# ProProject_Sheet1_2025-12-18.net
KiCad netlist of a schematic drawn in EasyEDA Pro
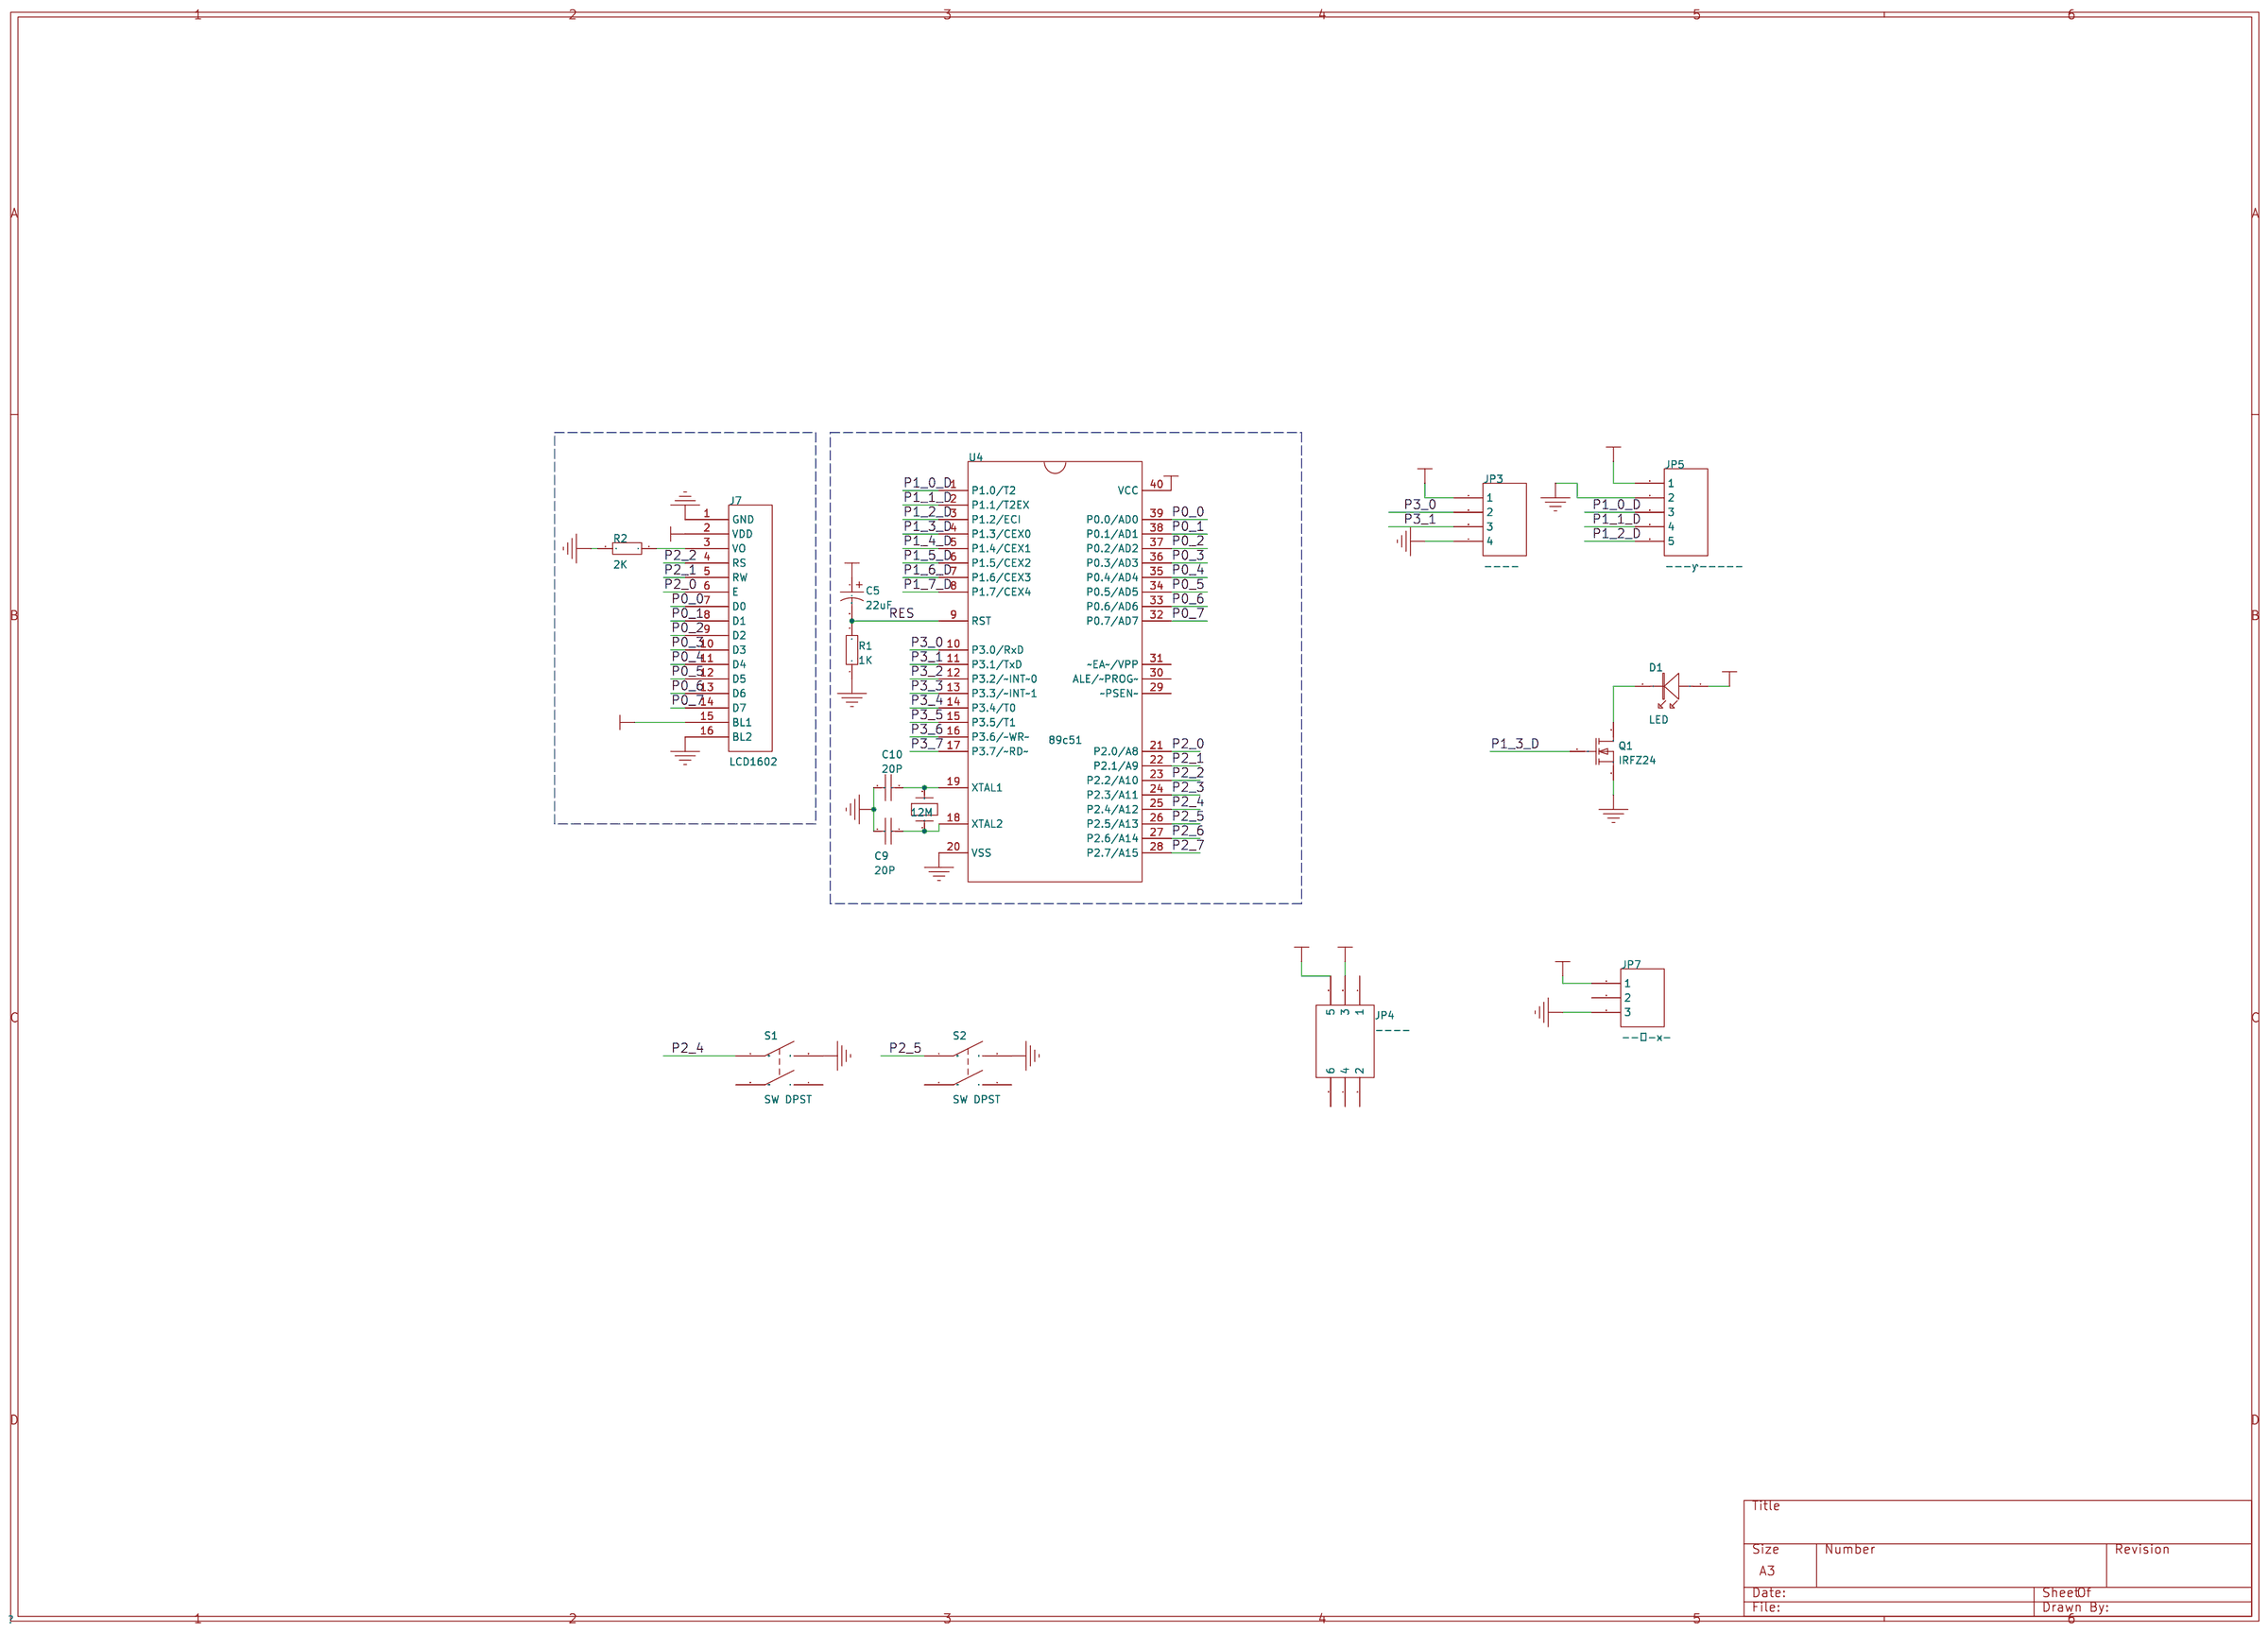
[diagram p0: schematic sheet]

(export (version "E")
  (design (tool "Eeschema 10.0.6"))
  (components
    (comp (ref "C5")
      (value "22uF")
      (description "Polarized Capacitor (Radial)")
      (fields (field (name "Publisher") "Altium Limited"))
      (libsource (lib "easyedapro") (part "Cap Pol1"))
    )
    (comp (ref "C9") (value "20P") (description "Capacitor") (libsource (lib "easyedapro") (part "CAP")))
    (comp (ref "C10") (value "20P") (description "Capacitor") (libsource (lib "easyedapro") (part "CAP")))
    (comp (ref "D1") (value "LED") (libsource (lib "easyedapro") (part "LED")))
    (comp (ref "J7") (value "LCD1602") (libsource (lib "easyedapro") (part "LCD1602")))
    (comp (ref "JP3")
      (value "----")
      (description "4 Pin Header")
      (libsource (lib "easyedapro") (part "4 HEADER"))
    )
    (comp (ref "JP4") (value "----") (libsource (lib "easyedapro") (part "HEADER 3X2")))
    (comp (ref "JP5") (value "---ƴ-----") (libsource (lib "easyedapro") (part "HEADER 5")))
    (comp (ref "JP7") (value "--Դ-ӿ-") (libsource (lib "easyedapro") (part "HEADER 3")))
    (comp (ref "Q1")
      (value "IRFZ24")
      (description "N-Channel MOSFET")
      (libsource (lib "easyedapro") (part "IRFZ24"))
    )
    (comp (ref "R1")
      (value "1K")
      (description "Resistor")
      (fields (field (name "Publisher") "Altium Limited"))
      (libsource (lib "easyedapro") (part "Res2"))
    )
    (comp (ref "R2")
      (value "2K")
      (description "Resistor")
      (fields (field (name "Publisher") "Altium Limited"))
      (libsource (lib "easyedapro") (part "Res2"))
    )
    (comp (ref "S1") (value "SW DPST") (libsource (lib "easyedapro") (part "SW DPST")))
    (comp (ref "S2") (value "SW DPST") (libsource (lib "easyedapro") (part "SW DPST")))
    (comp (ref "U4") (value "89c51") (libsource (lib "easyedapro") (part "89c51")))
    (comp (ref "Y4") (value "12M") (description "Crystal") (libsource (lib "easyedapro") (part "CRYSTAL")))
  )
  (nets
    (net (code "1") (name "/P0_0") (class "Default")
      (node (ref "J7") (pin "7") (pinfunction "D0_7") (pintype "unspecified"))
      (node (ref "U4") (pin "39") (pinfunction "P0.0/AD0_39") (pintype "bidirectional"))
    )
    (net (code "2") (name "/P0_1") (class "Default")
      (node (ref "J7") (pin "8") (pinfunction "D1_8") (pintype "unspecified"))
      (node (ref "U4") (pin "38") (pinfunction "P0.1/AD1_38") (pintype "bidirectional"))
    )
    (net (code "3") (name "/P0_2") (class "Default")
      (node (ref "J7") (pin "9") (pinfunction "D2_9") (pintype "unspecified"))
      (node (ref "U4") (pin "37") (pinfunction "P0.2/AD2_37") (pintype "bidirectional"))
    )
    (net (code "4") (name "/P0_3") (class "Default")
      (node (ref "J7") (pin "10") (pinfunction "D3_10") (pintype "unspecified"))
      (node (ref "U4") (pin "36") (pinfunction "P0.3/AD3_36") (pintype "bidirectional"))
    )
    (net (code "5") (name "/P0_4") (class "Default")
      (node (ref "J7") (pin "11") (pinfunction "D4_11") (pintype "unspecified"))
      (node (ref "U4") (pin "35") (pinfunction "P0.4/AD4_35") (pintype "bidirectional"))
    )
    (net (code "6") (name "/P0_5") (class "Default")
      (node (ref "J7") (pin "12") (pinfunction "D5_12") (pintype "unspecified"))
      (node (ref "U4") (pin "34") (pinfunction "P0.5/AD5_34") (pintype "bidirectional"))
    )
    (net (code "7") (name "/P0_6") (class "Default")
      (node (ref "J7") (pin "13") (pinfunction "D6_13") (pintype "unspecified"))
      (node (ref "U4") (pin "33") (pinfunction "P0.6/AD6_33") (pintype "bidirectional"))
    )
    (net (code "8") (name "/P0_7") (class "Default")
      (node (ref "J7") (pin "14") (pinfunction "D7_14") (pintype "unspecified"))
      (node (ref "U4") (pin "32") (pinfunction "P0.7/AD7_32") (pintype "bidirectional"))
    )
    (net (code "9") (name "/P1_0_D") (class "Default")
      (node (ref "JP5") (pin "3") (pinfunction "3_3") (pintype "unspecified"))
      (node (ref "U4") (pin "1") (pinfunction "P1.0/T2_1") (pintype "bidirectional"))
    )
    (net (code "10") (name "/P1_1_D") (class "Default")
      (node (ref "JP5") (pin "4") (pinfunction "4_4") (pintype "unspecified"))
      (node (ref "U4") (pin "2") (pinfunction "P1.1/T2EX_2") (pintype "bidirectional"))
    )
    (net (code "11") (name "/P1_2_D") (class "Default")
      (node (ref "JP5") (pin "5") (pinfunction "5_5") (pintype "unspecified"))
      (node (ref "U4") (pin "3") (pinfunction "P1.2/ECI_3") (pintype "bidirectional"))
    )
    (net (code "12") (name "/P1_3_D") (class "Default")
      (node (ref "Q1") (pin "1") (pinfunction "G_1") (pintype "input"))
      (node (ref "U4") (pin "4") (pinfunction "P1.3/CEX0_4") (pintype "bidirectional"))
    )
    (net (code "13") (name "/P1_4_D") (class "Default")
      (node (ref "U4") (pin "5") (pinfunction "P1.4/CEX1_5") (pintype "bidirectional"))
    )
    (net (code "14") (name "/P1_5_D") (class "Default")
      (node (ref "U4") (pin "6") (pinfunction "P1.5/CEX2_6") (pintype "bidirectional"))
    )
    (net (code "15") (name "/P1_6_D") (class "Default")
      (node (ref "U4") (pin "7") (pinfunction "P1.6/CEX3_7") (pintype "bidirectional"))
    )
    (net (code "16") (name "/P1_7_D") (class "Default")
      (node (ref "U4") (pin "8") (pinfunction "P1.7/CEX4_8") (pintype "bidirectional"))
    )
    (net (code "17") (name "/P2_0") (class "Default")
      (node (ref "J7") (pin "6") (pinfunction "E_6") (pintype "unspecified"))
      (node (ref "U4") (pin "21") (pinfunction "P2.0/A8_21") (pintype "bidirectional"))
    )
    (net (code "18") (name "/P2_1") (class "Default")
      (node (ref "J7") (pin "5") (pinfunction "RW_5") (pintype "unspecified"))
      (node (ref "U4") (pin "22") (pinfunction "P2.1/A9_22") (pintype "bidirectional"))
    )
    (net (code "19") (name "/P2_2") (class "Default")
      (node (ref "J7") (pin "4") (pinfunction "RS_4") (pintype "unspecified"))
      (node (ref "U4") (pin "23") (pinfunction "P2.2/A10_23") (pintype "bidirectional"))
    )
    (net (code "20") (name "/P2_3") (class "Default")
      (node (ref "U4") (pin "24") (pinfunction "P2.3/A11_24") (pintype "bidirectional"))
    )
    (net (code "21") (name "/P2_4") (class "Default")
      (node (ref "S1") (pin "1") (pinfunction "COMMON1_1") (pintype "unspecified"))
      (node (ref "U4") (pin "25") (pinfunction "P2.4/A12_25") (pintype "bidirectional"))
    )
    (net (code "22") (name "/P2_5") (class "Default")
      (node (ref "S2") (pin "1") (pinfunction "COMMON1_1") (pintype "unspecified"))
      (node (ref "U4") (pin "26") (pinfunction "P2.5/A13_26") (pintype "bidirectional"))
    )
    (net (code "23") (name "/P2_6") (class "Default")
      (node (ref "U4") (pin "27") (pinfunction "P2.6/A14_27") (pintype "bidirectional"))
    )
    (net (code "24") (name "/P2_7") (class "Default")
      (node (ref "U4") (pin "28") (pinfunction "P2.7/A15_28") (pintype "bidirectional"))
    )
    (net (code "25") (name "/P3_0") (class "Default")
      (node (ref "JP3") (pin "2") (pinfunction "2_2") (pintype "unspecified"))
      (node (ref "U4") (pin "10") (pinfunction "P3.0/RxD_10") (pintype "bidirectional"))
    )
    (net (code "26") (name "/P3_1") (class "Default")
      (node (ref "JP3") (pin "3") (pinfunction "3_3") (pintype "unspecified"))
      (node (ref "U4") (pin "11") (pinfunction "P3.1/TxD_11") (pintype "bidirectional"))
    )
    (net (code "27") (name "/P3_2") (class "Default")
      (node (ref "U4") (pin "12") (pinfunction "P3.2/~INT~0_12") (pintype "bidirectional"))
    )
    (net (code "28") (name "/P3_3") (class "Default")
      (node (ref "U4") (pin "13") (pinfunction "P3.3/~INT~1_13") (pintype "bidirectional"))
    )
    (net (code "29") (name "/P3_4") (class "Default")
      (node (ref "U4") (pin "14") (pinfunction "P3.4/T0_14") (pintype "bidirectional"))
    )
    (net (code "30") (name "/P3_5") (class "Default")
      (node (ref "U4") (pin "15") (pinfunction "P3.5/T1_15") (pintype "bidirectional"))
    )
    (net (code "31") (name "/P3_6") (class "Default")
      (node (ref "U4") (pin "16") (pinfunction "P3.6/~WR~_16") (pintype "bidirectional"))
    )
    (net (code "32") (name "/P3_7") (class "Default")
      (node (ref "U4") (pin "17") (pinfunction "P3.7/~RD~_17") (pintype "bidirectional"))
    )
    (net (code "33") (name "/RES") (class "Default")
      (node (ref "C5") (pin "2") (pinfunction "2_2") (pintype "unspecified"))
      (node (ref "R1") (pin "2") (pinfunction "2_2") (pintype "unspecified"))
      (node (ref "U4") (pin "9") (pinfunction "RST_9") (pintype "input"))
    )
    (net (code "34") (name "GND") (class "Default")
      (node (ref "C10") (pin "1") (pinfunction "1_1") (pintype "unspecified"))
      (node (ref "C9") (pin "2") (pinfunction "2_2") (pintype "unspecified"))
      (node (ref "J7") (pin "1") (pinfunction "GND_1") (pintype "unspecified"))
      (node (ref "J7") (pin "16") (pinfunction "BL2_16") (pintype "unspecified"))
      (node (ref "JP3") (pin "4") (pinfunction "4_4") (pintype "unspecified"))
      (node (ref "JP5") (pin "2") (pinfunction "2_2") (pintype "unspecified"))
      (node (ref "JP7") (pin "3") (pinfunction "3_3") (pintype "unspecified"))
      (node (ref "Q1") (pin "3") (pinfunction "S_3") (pintype "input"))
      (node (ref "R1") (pin "1") (pinfunction "1_1") (pintype "unspecified"))
      (node (ref "R2") (pin "2") (pinfunction "2_2") (pintype "unspecified"))
      (node (ref "S1") (pin "2") (pinfunction "NO1_2") (pintype "unspecified"))
      (node (ref "S2") (pin "2") (pinfunction "NO1_2") (pintype "unspecified"))
      (node (ref "U4") (pin "20") (pinfunction "VSS_20") (pintype "unspecified"))
    )
    (net (code "35") (name "Net-(J7-VO)") (class "Default")
      (node (ref "J7") (pin "3") (pinfunction "VO_3") (pintype "unspecified"))
      (node (ref "R2") (pin "1") (pinfunction "1_1") (pintype "unspecified"))
    )
    (net (code "36") (name "Net-(Q1-D)") (class "Default")
      (node (ref "D1") (pin "2") (pinfunction "2_2") (pintype "unspecified"))
      (node (ref "Q1") (pin "2") (pinfunction "D_2") (pintype "input"))
    )
    (net (code "37") (name "Net-(U4-XTAL1)") (class "Default")
      (node (ref "C10") (pin "2") (pinfunction "2_2") (pintype "unspecified"))
      (node (ref "U4") (pin "19") (pinfunction "XTAL1_19") (pintype "input"))
      (node (ref "Y4") (pin "2") (pinfunction "2_2") (pintype "unspecified"))
    )
    (net (code "38") (name "Net-(U4-XTAL2)") (class "Default")
      (node (ref "C9") (pin "1") (pinfunction "1_1") (pintype "unspecified"))
      (node (ref "U4") (pin "18") (pinfunction "XTAL2_18") (pintype "output"))
      (node (ref "Y4") (pin "1") (pinfunction "1_1") (pintype "unspecified"))
    )
    (net (code "39") (name "VCC") (class "Default")
      (node (ref "C5") (pin "1") (pinfunction "1_1") (pintype "unspecified"))
      (node (ref "D1") (pin "1") (pinfunction "1_1") (pintype "unspecified"))
      (node (ref "J7") (pin "15") (pinfunction "BL1_15") (pintype "unspecified"))
      (node (ref "J7") (pin "2") (pinfunction "VDD_2") (pintype "unspecified"))
      (node (ref "JP3") (pin "1") (pinfunction "1_1") (pintype "unspecified"))
      (node (ref "JP4") (pin "3") (pinfunction "3_3") (pintype "unspecified"))
      (node (ref "JP5") (pin "1") (pinfunction "1_1") (pintype "unspecified"))
      (node (ref "U4") (pin "40") (pinfunction "VCC_40") (pintype "unspecified"))
    )
    (net (code "40") (name "VIN") (class "Default")
      (node (ref "JP4") (pin "5") (pinfunction "5_5") (pintype "unspecified"))
      (node (ref "JP7") (pin "1") (pinfunction "1_1") (pintype "unspecified"))
    )
    (net (code "41") (name "unconnected-(JP4-Pad1)") (class "Default")
      (node (ref "JP4") (pin "1") (pinfunction "1_1") (pintype "unspecified"))
    )
    (net (code "42") (name "unconnected-(JP4-Pad2)") (class "Default")
      (node (ref "JP4") (pin "2") (pinfunction "2_2") (pintype "unspecified"))
    )
    (net (code "43") (name "unconnected-(JP4-Pad4)") (class "Default")
      (node (ref "JP4") (pin "4") (pinfunction "4_4") (pintype "unspecified"))
    )
    (net (code "44") (name "unconnected-(JP4-Pad6)") (class "Default")
      (node (ref "JP4") (pin "6") (pinfunction "6_6") (pintype "unspecified"))
    )
    (net (code "45") (name "unconnected-(JP7-Pad2)") (class "Default")
      (node (ref "JP7") (pin "2") (pinfunction "2_2") (pintype "unspecified"))
    )
    (net (code "46") (name "unconnected-(S1-COMMON2-Pad3)") (class "Default")
      (node (ref "S1") (pin "3") (pinfunction "COMMON2_3") (pintype "unspecified"))
    )
    (net (code "47") (name "unconnected-(S1-NO2-Pad4)") (class "Default")
      (node (ref "S1") (pin "4") (pinfunction "NO2_4") (pintype "unspecified"))
    )
    (net (code "48") (name "unconnected-(S2-COMMON2-Pad3)") (class "Default")
      (node (ref "S2") (pin "3") (pinfunction "COMMON2_3") (pintype "unspecified"))
    )
    (net (code "49") (name "unconnected-(S2-NO2-Pad4)") (class "Default")
      (node (ref "S2") (pin "4") (pinfunction "NO2_4") (pintype "unspecified"))
    )
    (net (code "50") (name "unconnected-(U4-ALE{slash}~PROG~-Pad30)") (class "Default")
      (node (ref "U4") (pin "30") (pinfunction "ALE/~PROG~_30") (pintype "bidirectional"))
    )
    (net (code "51") (name "unconnected-(U4-~EA~{slash}VPP-Pad31)") (class "Default")
      (node (ref "U4") (pin "31") (pinfunction "~EA~/VPP_31") (pintype "input"))
    )
    (net (code "52") (name "unconnected-(U4-~PSEN~-Pad29)") (class "Default")
      (node (ref "U4") (pin "29") (pinfunction "~PSEN~_29") (pintype "output"))
    )
  )
)
